# TCS3414_v0.net
KiCad netlist of a schematic drawn in EAGLE
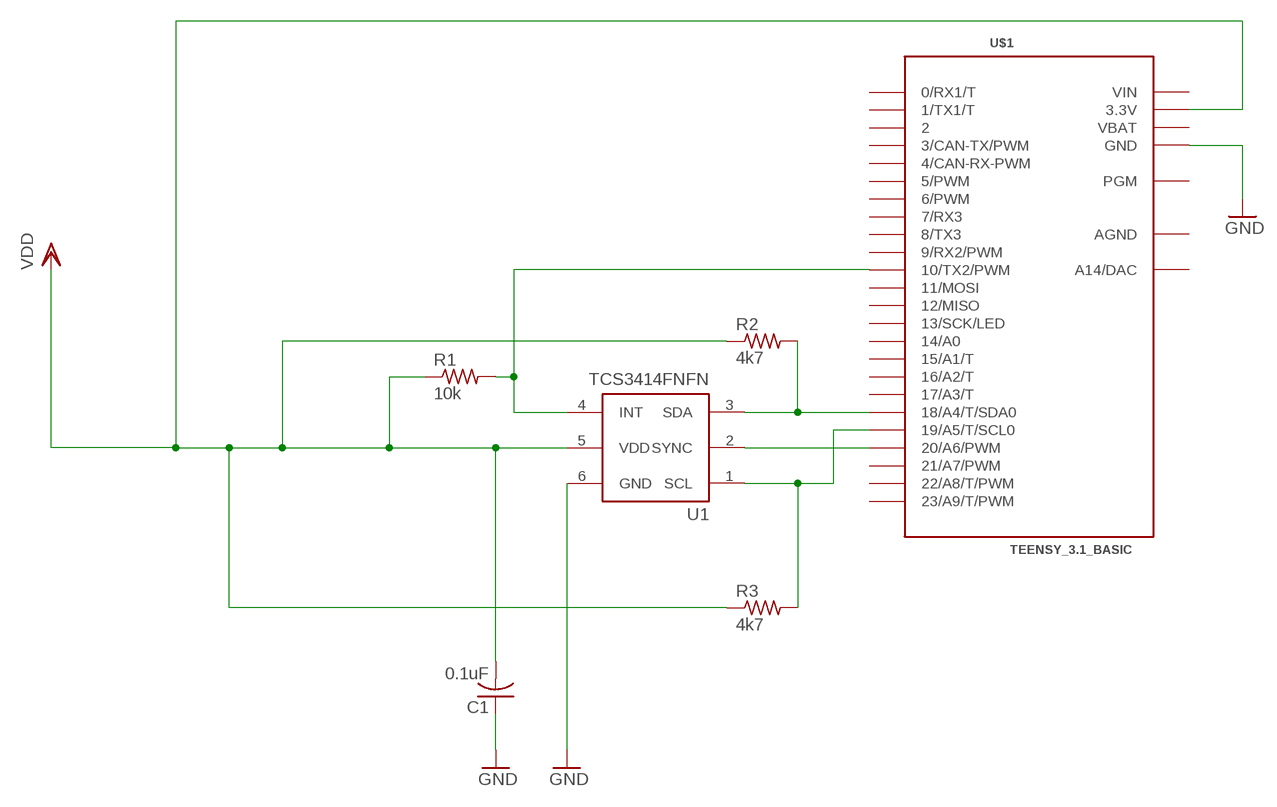
[diagram p0: schematic, sheet 1]

(export (version "E")
  (design (tool "Eeschema 10.0.6"))
  (components
    (comp (ref "C1")
      (value "0.1uF")
      (footprint "eagle-import:C0603")
      (libsource (lib "eagle-import") (part "C-USC0603"))
    )
    (comp (ref "R1")
      (value "10k")
      (footprint "eagle-import:R0603")
      (libsource (lib "eagle-import") (part "R-US_R0603"))
    )
    (comp (ref "R2")
      (value "4k7")
      (footprint "eagle-import:R0603")
      (libsource (lib "eagle-import") (part "R-US_R0603"))
    )
    (comp (ref "R3")
      (value "4k7")
      (footprint "eagle-import:R0603")
      (libsource (lib "eagle-import") (part "R-US_R0603"))
    )
    (comp (ref "U$1")
      (value "TEENSY_3.1_BASIC")
      (footprint "eagle-import:TEENSY_3.1_BASIC")
      (libsource (lib "eagle-import") (part "TEENSY_3.1_BASIC"))
    )
    (comp (ref "U1")
      (value "TCS3414FNFN")
      (footprint "eagle-import:TCS3414FN")
      (libsource (lib "eagle-import") (part "TCS3414FNFN"))
    )
  )
  (nets
    (net (code "1") (name "/AGND") (class "Default")
      (node (ref "U$1") (pin "AGND") (pinfunction "AGND_AGND") (pintype "power_in"))
    )
    (net (code "2") (name "/VBAT") (class "Default")
      (node (ref "U$1") (pin "VBAT") (pinfunction "VBAT_VBAT") (pintype "power_in"))
    )
    (net (code "3") (name "/VIN") (class "Default")
      (node (ref "U$1") (pin "VIN") (pinfunction "VIN_VIN") (pintype "power_in"))
    )
    (net (code "4") (name "GND") (class "Default")
      (node (ref "C1") (pin "1") (pinfunction "1_1") (pintype "passive"))
      (node (ref "U$1") (pin "GND") (pinfunction "GND_GND") (pintype "power_in"))
      (node (ref "U$1") (pin "GND1") (pinfunction "GND_GND1") (pintype "power_in"))
      (node (ref "U1") (pin "6") (pinfunction "GND_6") (pintype "bidirectional"))
    )
    (net (code "5") (name "Net-(U$1-10{slash}TX2{slash}PWM)") (class "Default")
      (node (ref "R1") (pin "2") (pinfunction "2_2") (pintype "passive"))
      (node (ref "U$1") (pin "10") (pinfunction "10/TX2/PWM_10") (pintype "bidirectional"))
      (node (ref "U1") (pin "4") (pinfunction "INT_4") (pintype "bidirectional"))
    )
    (net (code "6") (name "Net-(U$1-18{slash}A4{slash}T{slash}SDA0)") (class "Default")
      (node (ref "R2") (pin "2") (pinfunction "2_2") (pintype "passive"))
      (node (ref "U$1") (pin "18/A4") (pinfunction "18/A4/T/SDA0_18/A4") (pintype "bidirectional"))
      (node (ref "U1") (pin "3") (pinfunction "SDA_3") (pintype "bidirectional"))
    )
    (net (code "7") (name "Net-(U$1-19{slash}A5{slash}T{slash}SCL0)") (class "Default")
      (node (ref "R3") (pin "2") (pinfunction "2_2") (pintype "passive"))
      (node (ref "U$1") (pin "19/A5") (pinfunction "19/A5/T/SCL0_19/A5") (pintype "bidirectional"))
      (node (ref "U1") (pin "1") (pinfunction "SCL_1") (pintype "bidirectional"))
    )
    (net (code "8") (name "Net-(U$1-20{slash}A6{slash}PWM)") (class "Default")
      (node (ref "U$1") (pin "20/A6") (pinfunction "20/A6/PWM_20/A6") (pintype "bidirectional"))
      (node (ref "U1") (pin "2") (pinfunction "SYNC_2") (pintype "bidirectional"))
    )
    (net (code "9") (name "VDD") (class "Default")
      (node (ref "C1") (pin "2") (pinfunction "2_2") (pintype "passive"))
      (node (ref "R1") (pin "1") (pinfunction "1_1") (pintype "passive"))
      (node (ref "R2") (pin "1") (pinfunction "1_1") (pintype "passive"))
      (node (ref "R3") (pin "1") (pinfunction "1_1") (pintype "passive"))
      (node (ref "U$1") (pin "3.3V") (pinfunction "3.3V_3.3V") (pintype "power_in"))
      (node (ref "U$1") (pin "3.3V1") (pinfunction "3.3V_3.3V1") (pintype "power_in"))
      (node (ref "U1") (pin "5") (pinfunction "VDD_5") (pintype "bidirectional"))
    )
    (net (code "10") (name "unconnected-(U$1-0{slash}RX1{slash}T-Pad0)") (class "Default")
      (node (ref "U$1") (pin "0") (pinfunction "0/RX1/T_0") (pintype "bidirectional"))
    )
    (net (code "11") (name "unconnected-(U$1-1{slash}TX1{slash}T-Pad1)") (class "Default")
      (node (ref "U$1") (pin "1") (pinfunction "1/TX1/T_1") (pintype "bidirectional"))
    )
    (net (code "12") (name "unconnected-(U$1-3{slash}CAN-TX{slash}PWM-Pad3)") (class "Default")
      (node (ref "U$1") (pin "3") (pinfunction "3/CAN-TX/PWM_3") (pintype "bidirectional"))
    )
    (net (code "13") (name "unconnected-(U$1-4{slash}CAN-RX-PWM-Pad4)") (class "Default")
      (node (ref "U$1") (pin "4") (pinfunction "4/CAN-RX-PWM_4") (pintype "bidirectional"))
    )
    (net (code "14") (name "unconnected-(U$1-5{slash}PWM-Pad5)") (class "Default")
      (node (ref "U$1") (pin "5") (pinfunction "5/PWM_5") (pintype "bidirectional"))
    )
    (net (code "15") (name "unconnected-(U$1-6{slash}PWM-Pad6)") (class "Default")
      (node (ref "U$1") (pin "6") (pinfunction "6/PWM_6") (pintype "bidirectional"))
    )
    (net (code "16") (name "unconnected-(U$1-7{slash}RX3-Pad7)") (class "Default")
      (node (ref "U$1") (pin "7") (pinfunction "7/RX3_7") (pintype "bidirectional"))
    )
    (net (code "17") (name "unconnected-(U$1-8{slash}TX3-Pad8)") (class "Default")
      (node (ref "U$1") (pin "8") (pinfunction "8/TX3_8") (pintype "bidirectional"))
    )
    (net (code "18") (name "unconnected-(U$1-9{slash}RX2{slash}PWM-Pad9)") (class "Default")
      (node (ref "U$1") (pin "9") (pinfunction "9/RX2/PWM_9") (pintype "bidirectional"))
    )
    (net (code "19") (name "unconnected-(U$1-11{slash}MOSI-Pad11)") (class "Default")
      (node (ref "U$1") (pin "11") (pinfunction "11/MOSI_11") (pintype "bidirectional"))
    )
    (net (code "20") (name "unconnected-(U$1-12{slash}MISO-Pad12)") (class "Default")
      (node (ref "U$1") (pin "12") (pinfunction "12/MISO_12") (pintype "bidirectional"))
    )
    (net (code "21") (name "unconnected-(U$1-13{slash}SCK{slash}LED-Pad13)") (class "Default")
      (node (ref "U$1") (pin "13") (pinfunction "13/SCK/LED_13") (pintype "bidirectional"))
    )
    (net (code "22") (name "unconnected-(U$1-15{slash}A1{slash}T-Pad15{slash}A1)") (class "Default")
      (node (ref "U$1") (pin "15/A1") (pinfunction "15/A1/T_15/A1") (pintype "bidirectional"))
    )
    (net (code "23") (name "unconnected-(U$1-16{slash}A2{slash}T-Pad16{slash}A2)") (class "Default")
      (node (ref "U$1") (pin "16/A2") (pinfunction "16/A2/T_16/A2") (pintype "bidirectional"))
    )
    (net (code "24") (name "unconnected-(U$1-17{slash}A3{slash}T-Pad17{slash}A3)") (class "Default")
      (node (ref "U$1") (pin "17/A3") (pinfunction "17/A3/T_17/A3") (pintype "bidirectional"))
    )
    (net (code "25") (name "unconnected-(U$1-21{slash}A7{slash}PWM-Pad21{slash}A7)") (class "Default")
      (node (ref "U$1") (pin "21/A7") (pinfunction "21/A7/PWM_21/A7") (pintype "bidirectional"))
    )
    (net (code "26") (name "unconnected-(U$1-22{slash}A8{slash}T{slash}PWM-Pad22{slash}A8)") (class "Default")
      (node (ref "U$1") (pin "22/A8") (pinfunction "22/A8/T/PWM_22/A8") (pintype "bidirectional"))
    )
    (net (code "27") (name "unconnected-(U$1-23{slash}A9{slash}T{slash}PWM-Pad23{slash}A9)") (class "Default")
      (node (ref "U$1") (pin "23/A9") (pinfunction "23/A9/T/PWM_23/A9") (pintype "bidirectional"))
    )
    (net (code "28") (name "unconnected-(U$1-A14{slash}DAC-PadA14)") (class "Default")
      (node (ref "U$1") (pin "A14") (pinfunction "A14/DAC_A14") (pintype "bidirectional"))
    )
    (net (code "29") (name "unconnected-(U$1-Pad2)") (class "Default")
      (node (ref "U$1") (pin "2") (pinfunction "2_2") (pintype "bidirectional"))
    )
    (net (code "30") (name "unconnected-(U$1-Pad14{slash}A0)") (class "Default")
      (node (ref "U$1") (pin "14/A0") (pinfunction "14/A0_14/A0") (pintype "bidirectional"))
    )
    (net (code "31") (name "unconnected-(U$1-PadPGM)") (class "Default")
      (node (ref "U$1") (pin "PGM") (pinfunction "PGM_PGM") (pintype "bidirectional"))
    )
  )
)
